# 3_Regulator_5V_3V3.net
KiCad netlist of a schematic drawn in Altium Designer
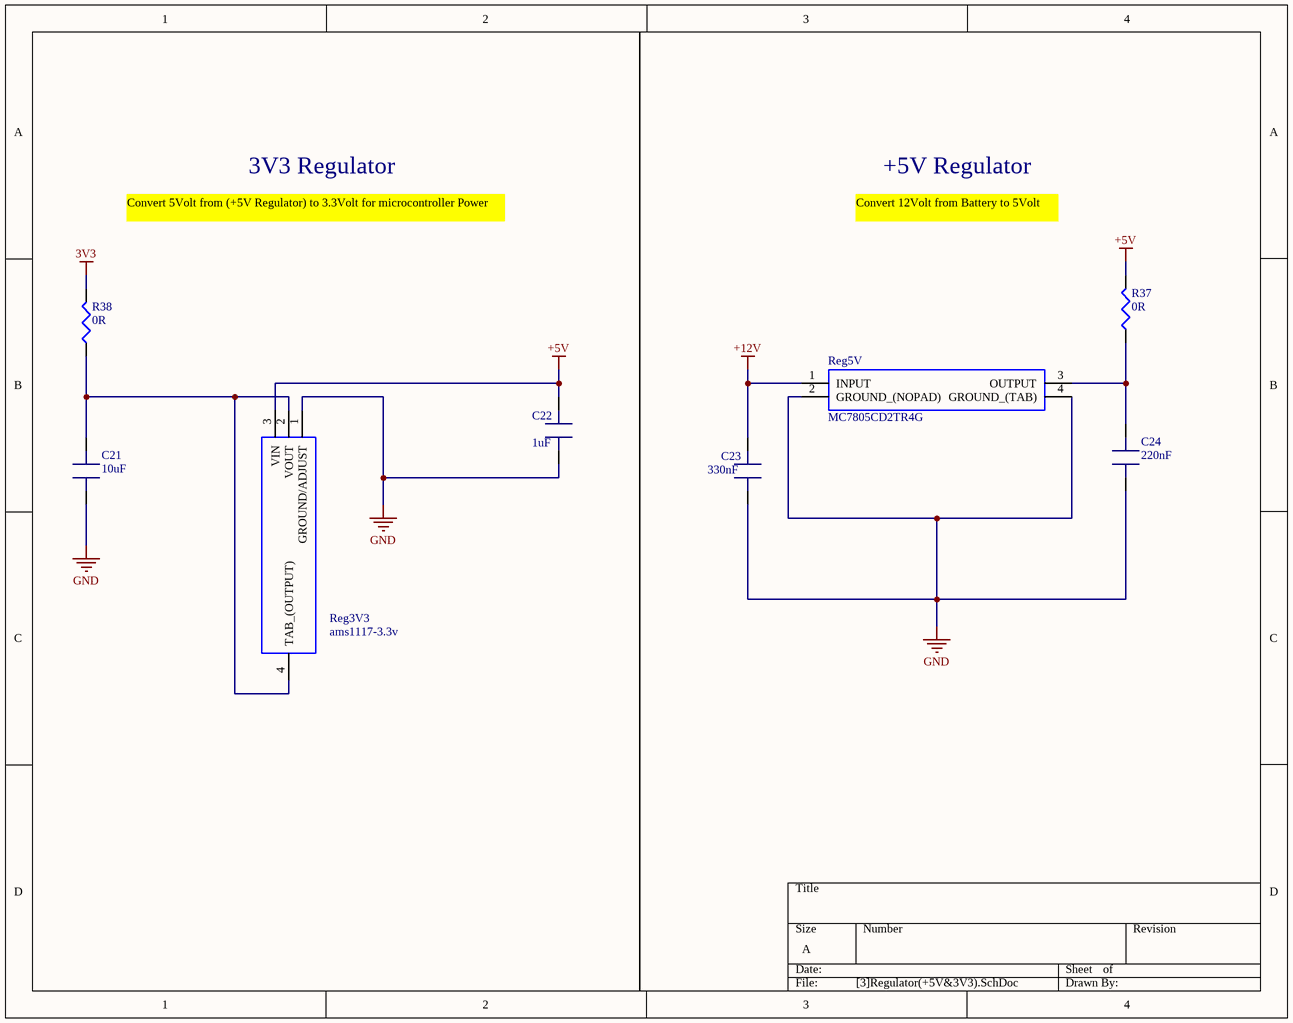
[diagram p0: [3]Regulator(+5V&3V3).SchDoc]

(export (version "E")
  (design (tool "Eeschema 10.0.6"))
  (components
    (comp (ref "C21") (value "10uF") (footprint "cap_805") (libsource (lib "CM") (part "cap805")))
    (comp (ref "C22") (value "1uF") (footprint "cap_805") (libsource (lib "CM") (part "cap805")))
    (comp (ref "C23") (value "330nF") (footprint "cap_805") (libsource (lib "CM") (part "cap805")))
    (comp (ref "C24") (value "220nF") (footprint "cap_805") (libsource (lib "CM") (part "cap805")))
    (comp (ref "R37") (value "0R") (footprint "Res805") (libsource (lib "Driver") (part "Res805")))
    (comp (ref "R38") (value "0R") (footprint "Res805") (libsource (lib "Driver") (part "Res805")))
    (comp (ref "Reg3V3")
      (value "ams1117-3.3v")
      (footprint "SOT229P700X180-4N")
      (description "1A LOW DROPOUT VOLTAGE REGULATOR, SOT-223")
      (libsource (lib "Driver") (part "ams1117-3.3v"))
    )
    (comp (ref "Reg5V")
      (value "MC7805CD2TR4G")
      (footprint "TO254P1420X457-4N")
      (fields (field (name "RS PART NUMBER") "1454706"))
      (libsource (lib "Driver") (part "MC7805CD2TR4G"))
    )
  )
  (nets
    (net (code "1") (name "+5V") (class "Default")
      (node (ref "C22") (pin "2") (pinfunction "2_2") (pintype "passive"))
      (node (ref "R37") (pin "2") (pinfunction "2_2") (pintype "passive"))
      (node (ref "Reg3V3") (pin "3") (pinfunction "VIN_3") (pintype "passive"))
    )
    (net (code "2") (name "+12V") (class "Default")
      (node (ref "C23") (pin "2") (pinfunction "2_2") (pintype "passive"))
      (node (ref "Reg5V") (pin "1") (pinfunction "INPUT_1") (pintype "passive"))
    )
    (net (code "3") (name "3V3") (class "Default")
      (node (ref "R38") (pin "2") (pinfunction "2_2") (pintype "passive"))
    )
    (net (code "4") (name "GND") (class "Default")
      (node (ref "C21") (pin "1") (pinfunction "1_1") (pintype "passive"))
      (node (ref "C22") (pin "1") (pinfunction "1_1") (pintype "passive"))
      (node (ref "C23") (pin "1") (pinfunction "1_1") (pintype "passive"))
      (node (ref "C24") (pin "1") (pinfunction "1_1") (pintype "passive"))
      (node (ref "Reg3V3") (pin "1") (pinfunction "GROUND/ADJUST_1") (pintype "passive"))
      (node (ref "Reg5V") (pin "2") (pinfunction "GROUND_(NOPAD)_2") (pintype "passive"))
      (node (ref "Reg5V") (pin "4") (pinfunction "GROUND_(TAB)_4") (pintype "passive"))
    )
    (net (code "5") (name "Net-(Reg3V3-TAB_(OUTPUT))") (class "Default")
      (node (ref "C21") (pin "2") (pinfunction "2_2") (pintype "passive"))
      (node (ref "R38") (pin "1") (pinfunction "1_1") (pintype "passive"))
      (node (ref "Reg3V3") (pin "2") (pinfunction "VOUT_2") (pintype "passive"))
      (node (ref "Reg3V3") (pin "4") (pinfunction "TAB_(OUTPUT)_4") (pintype "passive"))
    )
    (net (code "6") (name "Net-(Reg5V-OUTPUT)") (class "Default")
      (node (ref "C24") (pin "2") (pinfunction "2_2") (pintype "passive"))
      (node (ref "R37") (pin "1") (pinfunction "1_1") (pintype "passive"))
      (node (ref "Reg5V") (pin "3") (pinfunction "OUTPUT_3") (pintype "passive"))
    )
  )
)
